# board.net
KiCad netlist of a schematic drawn in EAGLE
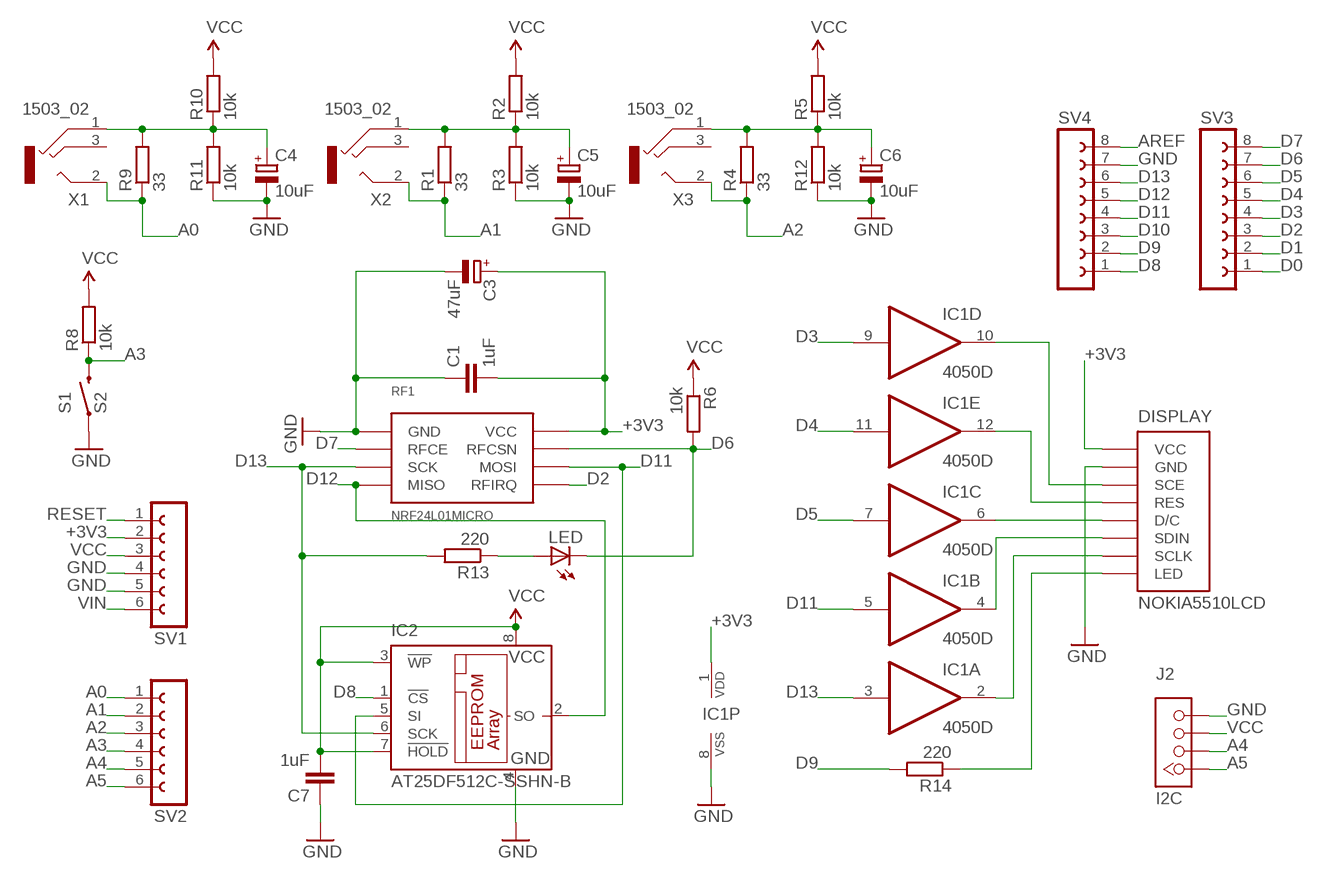
[diagram p0: schematic, sheet 1]

(export (version "E")
  (design (tool "Eeschema 10.0.6"))
  (components
    (comp (ref "C1")
      (value "1uF")
      (footprint "eagle-import:C0805")
      (libsource (lib "eagle-import") (part "C-EUC0805"))
    )
    (comp (ref "C3")
      (value "47uF")
      (footprint "eagle-import:153CLV-0405")
      (libsource (lib "eagle-import") (part "CPOL-EU153CLV-0405"))
    )
    (comp (ref "C4")
      (value "10uF")
      (footprint "eagle-import:153CLV-0405")
      (libsource (lib "eagle-import") (part "CPOL-EU153CLV-0405"))
    )
    (comp (ref "C5")
      (value "10uF")
      (footprint "eagle-import:153CLV-0405")
      (libsource (lib "eagle-import") (part "CPOL-EU153CLV-0405"))
    )
    (comp (ref "C6")
      (value "10uF")
      (footprint "eagle-import:153CLV-0405")
      (libsource (lib "eagle-import") (part "CPOL-EU153CLV-0405"))
    )
    (comp (ref "C7")
      (value "1uF")
      (footprint "eagle-import:C0805")
      (libsource (lib "eagle-import") (part "C-EUC0805"))
    )
    (comp (ref "DISPLAY")
      (value "NOKIA5510LCD")
      (footprint "eagle-import:NOKIA5510LCD-BLUE")
      (libsource (lib "eagle-import") (part "NOKIA5510LCD-BLUE"))
    )
    (comp (ref "IC1")
      (value "4050D")
      (footprint "eagle-import:SO16")
      (libsource (lib "eagle-import") (part "4050D"))
    )
    (comp (ref "IC2")
      (value "AT25DF512C-SSHN-B")
      (footprint "eagle-import:SO-08")
      (fields (field (name "MF") "MICROCHIP") (field (name "MPN") "25AA080/SN"))
      (libsource (lib "eagle-import") (part "25SNAA080"))
    )
    (comp (ref "J2")
      (value "I2C")
      (footprint "eagle-import:TWIG-4P-2.0C")
      (libsource (lib "eagle-import") (part "TWIG-4P-2.0C"))
    )
    (comp (ref "LED")
      (value "LEDCHIPLED_0805")
      (footprint "eagle-import:CHIPLED_0805")
      (libsource (lib "eagle-import") (part "LEDCHIPLED_0805"))
    )
    (comp (ref "R1")
      (value "33")
      (footprint "eagle-import:M0805")
      (libsource (lib "eagle-import") (part "R-EU_M0805"))
    )
    (comp (ref "R2")
      (value "10k")
      (footprint "eagle-import:M0805")
      (libsource (lib "eagle-import") (part "R-EU_M0805"))
    )
    (comp (ref "R3")
      (value "10k")
      (footprint "eagle-import:M0805")
      (libsource (lib "eagle-import") (part "R-EU_M0805"))
    )
    (comp (ref "R4")
      (value "33")
      (footprint "eagle-import:M0805")
      (libsource (lib "eagle-import") (part "R-EU_M0805"))
    )
    (comp (ref "R5")
      (value "10k")
      (footprint "eagle-import:M0805")
      (libsource (lib "eagle-import") (part "R-EU_M0805"))
    )
    (comp (ref "R6")
      (value "10k")
      (footprint "eagle-import:M0805")
      (libsource (lib "eagle-import") (part "R-EU_M0805"))
    )
    (comp (ref "R8")
      (value "10k")
      (footprint "eagle-import:M0805")
      (libsource (lib "eagle-import") (part "R-EU_M0805"))
    )
    (comp (ref "R9")
      (value "33")
      (footprint "eagle-import:M0805")
      (libsource (lib "eagle-import") (part "R-EU_M0805"))
    )
    (comp (ref "R10")
      (value "10k")
      (footprint "eagle-import:M0805")
      (libsource (lib "eagle-import") (part "R-EU_M0805"))
    )
    (comp (ref "R11")
      (value "10k")
      (footprint "eagle-import:M0805")
      (libsource (lib "eagle-import") (part "R-EU_M0805"))
    )
    (comp (ref "R12")
      (value "10k")
      (footprint "eagle-import:M0805")
      (libsource (lib "eagle-import") (part "R-EU_M0805"))
    )
    (comp (ref "R13")
      (value "220")
      (footprint "eagle-import:M0805")
      (libsource (lib "eagle-import") (part "R-EU_M0805"))
    )
    (comp (ref "R14")
      (value "220")
      (footprint "eagle-import:M0805")
      (libsource (lib "eagle-import") (part "R-EU_M0805"))
    )
    (comp (ref "RF1")
      (value "NRF24L01MICRO")
      (footprint "eagle-import:MICRO-RF24")
      (libsource (lib "eagle-import") (part "NRF24L01MICRO"))
    )
    (comp (ref "S1")
      (value "S2")
      (footprint "eagle-import:TACTILE-PTH-SIDEEZ")
      (libsource (lib "eagle-import") (part "SWITCH-MOMENTARY-2SIDE_EZ"))
    )
    (comp (ref "SV1")
      (value "FE06-1")
      (footprint "eagle-import:FE06")
      (libsource (lib "eagle-import") (part "FE06-1"))
    )
    (comp (ref "SV2")
      (value "FE06-1")
      (footprint "eagle-import:FE06")
      (libsource (lib "eagle-import") (part "FE06-1"))
    )
    (comp (ref "SV3")
      (value "FE08-1")
      (footprint "eagle-import:FE08")
      (libsource (lib "eagle-import") (part "FE08-1"))
    )
    (comp (ref "SV4")
      (value "FE08-1")
      (footprint "eagle-import:FE08")
      (libsource (lib "eagle-import") (part "FE08-1"))
    )
    (comp (ref "X1")
      (value "1503_02")
      (footprint "eagle-import:1503_02")
      (libsource (lib "eagle-import") (part "1503_02"))
    )
    (comp (ref "X2")
      (value "1503_02")
      (footprint "eagle-import:1503_02")
      (libsource (lib "eagle-import") (part "1503_02"))
    )
    (comp (ref "X3")
      (value "1503_02")
      (footprint "eagle-import:1503_02")
      (libsource (lib "eagle-import") (part "1503_02"))
    )
  )
  (nets
    (net (code "1") (name "/+3V3") (class "Default")
      (node (ref "C1") (pin "2") (pinfunction "2_2") (pintype "passive"))
      (node (ref "C3") (pin "+") (pinfunction "+_+") (pintype "passive"))
      (node (ref "DISPLAY") (pin "VCC") (pinfunction "VCC_VCC") (pintype "power_in"))
      (node (ref "IC1") (pin "1") (pinfunction "VDD_1") (pintype "power_in"))
      (node (ref "RF1") (pin "3V3") (pinfunction "VCC_3V3") (pintype "power_in"))
      (node (ref "SV1") (pin "2") (pinfunction "2_2") (pintype "passive"))
    )
    (net (code "2") (name "/A0") (class "Default")
      (node (ref "R9") (pin "1") (pinfunction "1_1") (pintype "passive"))
      (node (ref "SV2") (pin "1") (pinfunction "1_1") (pintype "passive"))
      (node (ref "X1") (pin "2") (pinfunction "2_2") (pintype "passive"))
    )
    (net (code "3") (name "/A1") (class "Default")
      (node (ref "R1") (pin "1") (pinfunction "1_1") (pintype "passive"))
      (node (ref "SV2") (pin "2") (pinfunction "2_2") (pintype "passive"))
      (node (ref "X2") (pin "2") (pinfunction "2_2") (pintype "passive"))
    )
    (net (code "4") (name "/A2") (class "Default")
      (node (ref "R4") (pin "1") (pinfunction "1_1") (pintype "passive"))
      (node (ref "SV2") (pin "3") (pinfunction "3_3") (pintype "passive"))
      (node (ref "X3") (pin "2") (pinfunction "2_2") (pintype "passive"))
    )
    (net (code "5") (name "/A3") (class "Default")
      (node (ref "R8") (pin "1") (pinfunction "1_1") (pintype "passive"))
      (node (ref "S1") (pin "2") (pinfunction "2_2") (pintype "passive"))
      (node (ref "SV2") (pin "4") (pinfunction "4_4") (pintype "passive"))
    )
    (net (code "6") (name "/A4") (class "Default")
      (node (ref "J2") (pin "P$2") (pinfunction "P$2_P$2") (pintype "bidirectional"))
      (node (ref "SV2") (pin "5") (pinfunction "5_5") (pintype "passive"))
    )
    (net (code "7") (name "/A5") (class "Default")
      (node (ref "J2") (pin "P$1") (pinfunction "P$1_P$1") (pintype "bidirectional"))
      (node (ref "SV2") (pin "6") (pinfunction "6_6") (pintype "passive"))
    )
    (net (code "8") (name "/AREF") (class "Default")
      (node (ref "SV4") (pin "8") (pinfunction "8_8") (pintype "passive"))
    )
    (net (code "9") (name "/D0") (class "Default")
      (node (ref "SV3") (pin "1") (pinfunction "1_1") (pintype "passive"))
    )
    (net (code "10") (name "/D1") (class "Default")
      (node (ref "SV3") (pin "2") (pinfunction "2_2") (pintype "passive"))
    )
    (net (code "11") (name "/D2") (class "Default")
      (node (ref "RF1") (pin "IRQ") (pinfunction "RFIRQ_IRQ") (pintype "output"))
      (node (ref "SV3") (pin "3") (pinfunction "3_3") (pintype "passive"))
    )
    (net (code "12") (name "/D3") (class "Default")
      (node (ref "IC1") (pin "9") (pinfunction "I_9") (pintype "input"))
      (node (ref "SV3") (pin "4") (pinfunction "4_4") (pintype "passive"))
    )
    (net (code "13") (name "/D4") (class "Default")
      (node (ref "IC1") (pin "11") (pinfunction "I_11") (pintype "input"))
      (node (ref "SV3") (pin "5") (pinfunction "5_5") (pintype "passive"))
    )
    (net (code "14") (name "/D5") (class "Default")
      (node (ref "IC1") (pin "7") (pinfunction "I_7") (pintype "input"))
      (node (ref "SV3") (pin "6") (pinfunction "6_6") (pintype "passive"))
    )
    (net (code "15") (name "/D6") (class "Default")
      (node (ref "LED") (pin "C") (pinfunction "C_C") (pintype "passive"))
      (node (ref "R6") (pin "2") (pinfunction "2_2") (pintype "passive"))
      (node (ref "RF1") (pin "CSN") (pinfunction "RFCSN_CSN") (pintype "bidirectional"))
      (node (ref "SV3") (pin "7") (pinfunction "7_7") (pintype "passive"))
    )
    (net (code "16") (name "/D7") (class "Default")
      (node (ref "RF1") (pin "CE") (pinfunction "RFCE_CE") (pintype "input"))
      (node (ref "SV3") (pin "8") (pinfunction "8_8") (pintype "passive"))
    )
    (net (code "17") (name "/D8") (class "Default")
      (node (ref "IC2") (pin "1") (pinfunction "~{CS}_1") (pintype "input"))
      (node (ref "SV4") (pin "1") (pinfunction "1_1") (pintype "passive"))
    )
    (net (code "18") (name "/D9") (class "Default")
      (node (ref "R14") (pin "2") (pinfunction "2_2") (pintype "passive"))
      (node (ref "SV4") (pin "2") (pinfunction "2_2") (pintype "passive"))
    )
    (net (code "19") (name "/D10") (class "Default")
      (node (ref "SV4") (pin "3") (pinfunction "3_3") (pintype "passive"))
    )
    (net (code "20") (name "/D11") (class "Default")
      (node (ref "IC1") (pin "5") (pinfunction "I_5") (pintype "input"))
      (node (ref "IC2") (pin "5") (pinfunction "SI_5") (pintype "input"))
      (node (ref "RF1") (pin "MOSI") (pinfunction "MOSI_MOSI") (pintype "bidirectional"))
      (node (ref "SV4") (pin "4") (pinfunction "4_4") (pintype "passive"))
    )
    (net (code "21") (name "/D12") (class "Default")
      (node (ref "IC2") (pin "2") (pinfunction "SO_2") (pintype "bidirectional"))
      (node (ref "RF1") (pin "MISO") (pinfunction "MISO_MISO") (pintype "bidirectional"))
      (node (ref "SV4") (pin "5") (pinfunction "5_5") (pintype "passive"))
    )
    (net (code "22") (name "/D13") (class "Default")
      (node (ref "IC1") (pin "3") (pinfunction "I_3") (pintype "input"))
      (node (ref "IC2") (pin "6") (pinfunction "SCK_6") (pintype "input"))
      (node (ref "R13") (pin "2") (pinfunction "2_2") (pintype "passive"))
      (node (ref "RF1") (pin "SCK") (pinfunction "SCK_SCK") (pintype "input"))
      (node (ref "SV4") (pin "6") (pinfunction "6_6") (pintype "passive"))
    )
    (net (code "23") (name "/RESET") (class "Default")
      (node (ref "SV1") (pin "1") (pinfunction "1_1") (pintype "passive"))
    )
    (net (code "24") (name "/VIN") (class "Default")
      (node (ref "SV1") (pin "6") (pinfunction "6_6") (pintype "passive"))
    )
    (net (code "25") (name "GND") (class "Default")
      (node (ref "C1") (pin "1") (pinfunction "1_1") (pintype "passive"))
      (node (ref "C3") (pin "-") (pinfunction "-_-") (pintype "passive"))
      (node (ref "C4") (pin "-") (pinfunction "-_-") (pintype "passive"))
      (node (ref "C5") (pin "-") (pinfunction "-_-") (pintype "passive"))
      (node (ref "C6") (pin "-") (pinfunction "-_-") (pintype "passive"))
      (node (ref "C7") (pin "1") (pinfunction "1_1") (pintype "passive"))
      (node (ref "DISPLAY") (pin "GND") (pinfunction "GND_GND") (pintype "power_in"))
      (node (ref "IC1") (pin "8") (pinfunction "VSS_8") (pintype "power_in"))
      (node (ref "IC2") (pin "4") (pinfunction "GND_4") (pintype "power_in"))
      (node (ref "J2") (pin "P$4") (pinfunction "P$4_P$4") (pintype "bidirectional"))
      (node (ref "R11") (pin "1") (pinfunction "1_1") (pintype "passive"))
      (node (ref "R12") (pin "1") (pinfunction "1_1") (pintype "passive"))
      (node (ref "R3") (pin "1") (pinfunction "1_1") (pintype "passive"))
      (node (ref "RF1") (pin "GND") (pinfunction "GND_GND") (pintype "power_in"))
      (node (ref "S1") (pin "1") (pinfunction "1_1") (pintype "passive"))
      (node (ref "SV1") (pin "4") (pinfunction "4_4") (pintype "passive"))
      (node (ref "SV1") (pin "5") (pinfunction "5_5") (pintype "passive"))
      (node (ref "SV4") (pin "7") (pinfunction "7_7") (pintype "passive"))
    )
    (net (code "26") (name "Net-(C4-Pad+)") (class "Default")
      (node (ref "C4") (pin "+") (pinfunction "+_+") (pintype "passive"))
      (node (ref "R10") (pin "1") (pinfunction "1_1") (pintype "passive"))
      (node (ref "R11") (pin "2") (pinfunction "2_2") (pintype "passive"))
      (node (ref "R9") (pin "2") (pinfunction "2_2") (pintype "passive"))
      (node (ref "X1") (pin "1") (pinfunction "1_1") (pintype "passive"))
    )
    (net (code "27") (name "Net-(C5-Pad+)") (class "Default")
      (node (ref "C5") (pin "+") (pinfunction "+_+") (pintype "passive"))
      (node (ref "R1") (pin "2") (pinfunction "2_2") (pintype "passive"))
      (node (ref "R2") (pin "1") (pinfunction "1_1") (pintype "passive"))
      (node (ref "R3") (pin "2") (pinfunction "2_2") (pintype "passive"))
      (node (ref "X2") (pin "1") (pinfunction "1_1") (pintype "passive"))
    )
    (net (code "28") (name "Net-(C6-Pad+)") (class "Default")
      (node (ref "C6") (pin "+") (pinfunction "+_+") (pintype "passive"))
      (node (ref "R12") (pin "2") (pinfunction "2_2") (pintype "passive"))
      (node (ref "R4") (pin "2") (pinfunction "2_2") (pintype "passive"))
      (node (ref "R5") (pin "1") (pinfunction "1_1") (pintype "passive"))
      (node (ref "X3") (pin "1") (pinfunction "1_1") (pintype "passive"))
    )
    (net (code "29") (name "Net-(DISPLAY-D{slash}C)") (class "Default")
      (node (ref "DISPLAY") (pin "DC") (pinfunction "D/C_DC") (pintype "input"))
      (node (ref "IC1") (pin "6") (pinfunction "O_6") (pintype "output"))
    )
    (net (code "30") (name "Net-(DISPLAY-LED)") (class "Default")
      (node (ref "DISPLAY") (pin "BL") (pinfunction "LED_BL") (pintype "input"))
      (node (ref "R14") (pin "1") (pinfunction "1_1") (pintype "passive"))
    )
    (net (code "31") (name "Net-(DISPLAY-RES)") (class "Default")
      (node (ref "DISPLAY") (pin "RST") (pinfunction "RES_RST") (pintype "input"))
      (node (ref "IC1") (pin "12") (pinfunction "O_12") (pintype "output"))
    )
    (net (code "32") (name "Net-(DISPLAY-SCE)") (class "Default")
      (node (ref "DISPLAY") (pin "CE") (pinfunction "SCE_CE") (pintype "input"))
      (node (ref "IC1") (pin "10") (pinfunction "O_10") (pintype "output"))
    )
    (net (code "33") (name "Net-(DISPLAY-SCLK)") (class "Default")
      (node (ref "DISPLAY") (pin "CLK") (pinfunction "SCLK_CLK") (pintype "input"))
      (node (ref "IC1") (pin "2") (pinfunction "O_2") (pintype "output"))
    )
    (net (code "34") (name "Net-(DISPLAY-SDIN)") (class "Default")
      (node (ref "DISPLAY") (pin "DIN") (pinfunction "SDIN_DIN") (pintype "input"))
      (node (ref "IC1") (pin "4") (pinfunction "O_4") (pintype "output"))
    )
    (net (code "35") (name "Net-(LED-PadA)") (class "Default")
      (node (ref "LED") (pin "A") (pinfunction "A_A") (pintype "passive"))
      (node (ref "R13") (pin "1") (pinfunction "1_1") (pintype "passive"))
    )
    (net (code "36") (name "VCC") (class "Default")
      (node (ref "C7") (pin "2") (pinfunction "2_2") (pintype "passive"))
      (node (ref "IC2") (pin "3") (pinfunction "~{WP}_3") (pintype "input"))
      (node (ref "IC2") (pin "7") (pinfunction "~{HOLD}_7") (pintype "input"))
      (node (ref "IC2") (pin "8") (pinfunction "VCC_8") (pintype "power_in"))
      (node (ref "J2") (pin "P$3") (pinfunction "P$3_P$3") (pintype "bidirectional"))
      (node (ref "R10") (pin "2") (pinfunction "2_2") (pintype "passive"))
      (node (ref "R2") (pin "2") (pinfunction "2_2") (pintype "passive"))
      (node (ref "R5") (pin "2") (pinfunction "2_2") (pintype "passive"))
      (node (ref "R6") (pin "1") (pinfunction "1_1") (pintype "passive"))
      (node (ref "R8") (pin "2") (pinfunction "2_2") (pintype "passive"))
      (node (ref "SV1") (pin "3") (pinfunction "3_3") (pintype "passive"))
    )
    (net (code "37") (name "unconnected-(X1-2-Pad2@2)") (class "Default")
      (node (ref "X1") (pin "2@2") (pinfunction "2_2@2") (pintype "passive"))
    )
    (net (code "38") (name "unconnected-(X1-Pad3)") (class "Default")
      (node (ref "X1") (pin "3") (pinfunction "3_3") (pintype "passive"))
    )
    (net (code "39") (name "unconnected-(X2-2-Pad2@2)") (class "Default")
      (node (ref "X2") (pin "2@2") (pinfunction "2_2@2") (pintype "passive"))
    )
    (net (code "40") (name "unconnected-(X2-Pad3)") (class "Default")
      (node (ref "X2") (pin "3") (pinfunction "3_3") (pintype "passive"))
    )
    (net (code "41") (name "unconnected-(X3-2-Pad2@2)") (class "Default")
      (node (ref "X3") (pin "2@2") (pinfunction "2_2@2") (pintype "passive"))
    )
    (net (code "42") (name "unconnected-(X3-Pad3)") (class "Default")
      (node (ref "X3") (pin "3") (pinfunction "3_3") (pintype "passive"))
    )
  )
)
